# proMinimotor.net
KiCad netlist of a schematic drawn in EAGLE
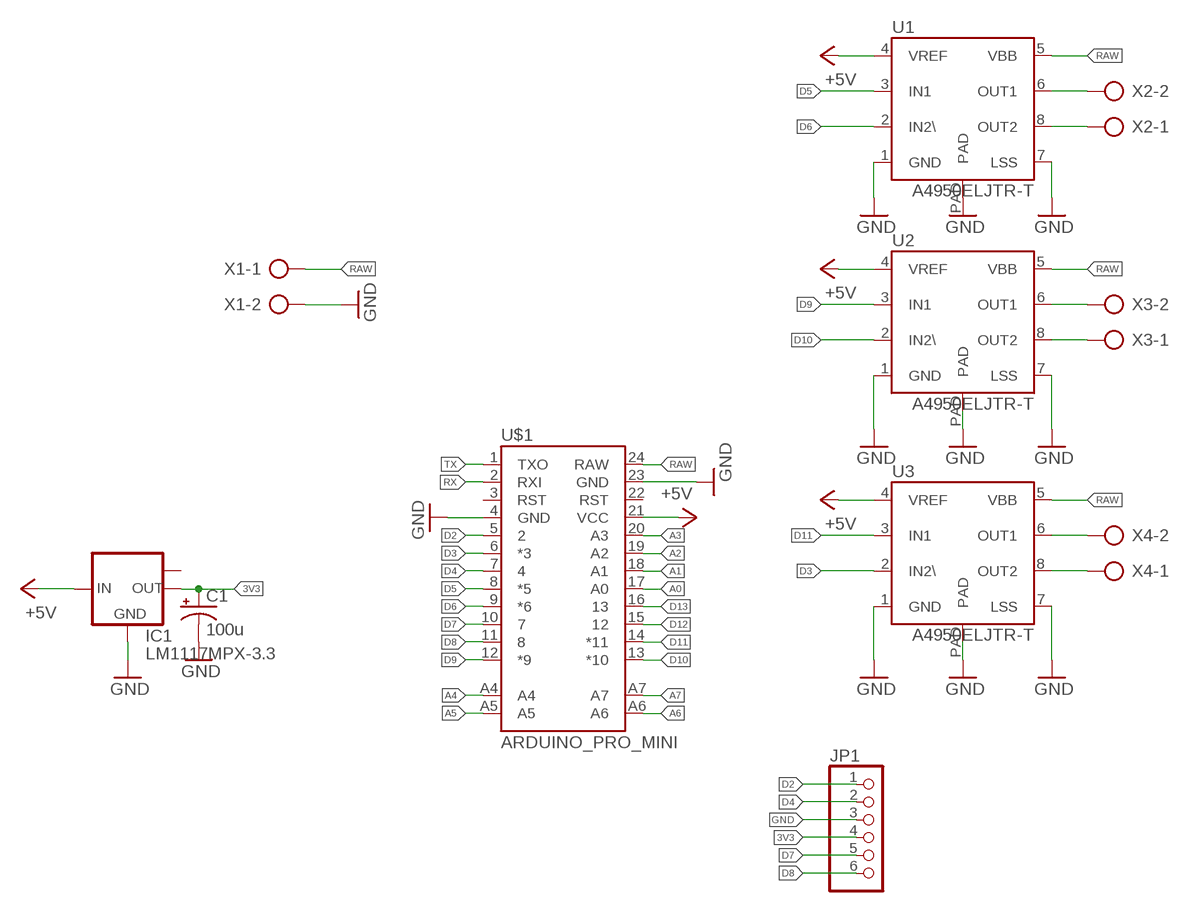
[diagram p0: schematic, sheet 1]

(export (version "E")
  (design (tool "Eeschema 10.0.6"))
  (components
    (comp (ref "C1")
      (value "100u")
      (footprint "eagle-import:E2,5-7")
      (libsource (lib "eagle-import") (part "CPOL-USE2.5-7"))
    )
    (comp (ref "IC1")
      (value "LM1117MPX-3.3")
      (footprint "eagle-import:SOT223")
      (libsource (lib "eagle-import") (part "LM1117MPX-3.3"))
    )
    (comp (ref "JP1")
      (value "PINHD-1X6/90")
      (footprint "eagle-import:1X06_90")
      (libsource (lib "eagle-import") (part "PINHD-1X6/90"))
    )
    (comp (ref "U$1")
      (value "ARDUINO_PRO_MINI")
      (footprint "eagle-import:ARDUINO_PRO_MINI")
      (libsource (lib "eagle-import") (part "ARDUINO_PRO_MINI"))
    )
    (comp (ref "U1")
      (value "A4950ELJTR-T")
      (footprint "eagle-import:SOIC8TP")
      (libsource (lib "eagle-import") (part "A4950ELJTR-T"))
    )
    (comp (ref "U2")
      (value "A4950ELJTR-T")
      (footprint "eagle-import:SOIC8TP")
      (libsource (lib "eagle-import") (part "A4950ELJTR-T"))
    )
    (comp (ref "U3")
      (value "A4950ELJTR-T")
      (footprint "eagle-import:SOIC8TP")
      (libsource (lib "eagle-import") (part "A4950ELJTR-T"))
    )
    (comp (ref "X1")
      (value "AK500/2")
      (footprint "eagle-import:AK500_2")
      (libsource (lib "eagle-import") (part "AK500/2"))
    )
    (comp (ref "X2")
      (value "AK500/2")
      (footprint "eagle-import:AK500_2")
      (libsource (lib "eagle-import") (part "AK500/2"))
    )
    (comp (ref "X3")
      (value "AK500/2")
      (footprint "eagle-import:AK500_2")
      (libsource (lib "eagle-import") (part "AK500/2"))
    )
    (comp (ref "X4")
      (value "AK500/2")
      (footprint "eagle-import:AK500_2")
      (libsource (lib "eagle-import") (part "AK500/2"))
    )
  )
  (nets
    (net (code "1") (name "+5V") (class "Default")
      (node (ref "IC1") (pin "3") (pinfunction "IN_3") (pintype "input"))
      (node (ref "U$1") (pin "21") (pinfunction "VCC_21") (pintype "bidirectional"))
      (node (ref "U1") (pin "4") (pinfunction "VREF_4") (pintype "bidirectional"))
      (node (ref "U2") (pin "4") (pinfunction "VREF_4") (pintype "bidirectional"))
      (node (ref "U3") (pin "4") (pinfunction "VREF_4") (pintype "bidirectional"))
    )
    (net (code "2") (name "3V3") (class "Default")
      (node (ref "C1") (pin "+") (pinfunction "+_+") (pintype "passive"))
      (node (ref "IC1") (pin "2") (pinfunction "OUT_2") (pintype "passive"))
      (node (ref "JP1") (pin "4") (pinfunction "4_4") (pintype "passive"))
    )
    (net (code "3") (name "A0") (class "Default")
      (node (ref "U$1") (pin "17") (pinfunction "A0_17") (pintype "bidirectional"))
    )
    (net (code "4") (name "A1") (class "Default")
      (node (ref "U$1") (pin "18") (pinfunction "A1_18") (pintype "bidirectional"))
    )
    (net (code "5") (name "A2") (class "Default")
      (node (ref "U$1") (pin "19") (pinfunction "A2_19") (pintype "bidirectional"))
    )
    (net (code "6") (name "A3") (class "Default")
      (node (ref "U$1") (pin "20") (pinfunction "A3_20") (pintype "bidirectional"))
    )
    (net (code "7") (name "A4") (class "Default")
      (node (ref "U$1") (pin "A4") (pinfunction "A4_A4") (pintype "bidirectional"))
    )
    (net (code "8") (name "A5") (class "Default")
      (node (ref "U$1") (pin "A5") (pinfunction "A5_A5") (pintype "bidirectional"))
    )
    (net (code "9") (name "A6") (class "Default")
      (node (ref "U$1") (pin "A6") (pinfunction "A6_A6") (pintype "bidirectional"))
    )
    (net (code "10") (name "A7") (class "Default")
      (node (ref "U$1") (pin "A7") (pinfunction "A7_A7") (pintype "bidirectional"))
    )
    (net (code "11") (name "D2") (class "Default")
      (node (ref "JP1") (pin "1") (pinfunction "1_1") (pintype "passive"))
      (node (ref "U$1") (pin "5") (pinfunction "2_5") (pintype "bidirectional"))
    )
    (net (code "12") (name "D3") (class "Default")
      (node (ref "U$1") (pin "6") (pinfunction "*3_6") (pintype "bidirectional"))
      (node (ref "U3") (pin "2") (pinfunction "IN2\\_2") (pintype "bidirectional"))
    )
    (net (code "13") (name "D4") (class "Default")
      (node (ref "JP1") (pin "2") (pinfunction "2_2") (pintype "passive"))
      (node (ref "U$1") (pin "7") (pinfunction "4_7") (pintype "bidirectional"))
    )
    (net (code "14") (name "D5") (class "Default")
      (node (ref "U$1") (pin "8") (pinfunction "*5_8") (pintype "bidirectional"))
      (node (ref "U1") (pin "3") (pinfunction "IN1_3") (pintype "bidirectional"))
    )
    (net (code "15") (name "D6") (class "Default")
      (node (ref "U$1") (pin "9") (pinfunction "*6_9") (pintype "bidirectional"))
      (node (ref "U1") (pin "2") (pinfunction "IN2\\_2") (pintype "bidirectional"))
    )
    (net (code "16") (name "D7") (class "Default")
      (node (ref "JP1") (pin "5") (pinfunction "5_5") (pintype "passive"))
      (node (ref "U$1") (pin "10") (pinfunction "7_10") (pintype "bidirectional"))
    )
    (net (code "17") (name "D8") (class "Default")
      (node (ref "JP1") (pin "6") (pinfunction "6_6") (pintype "passive"))
      (node (ref "U$1") (pin "11") (pinfunction "8_11") (pintype "bidirectional"))
    )
    (net (code "18") (name "D9") (class "Default")
      (node (ref "U$1") (pin "12") (pinfunction "*9_12") (pintype "bidirectional"))
      (node (ref "U2") (pin "3") (pinfunction "IN1_3") (pintype "bidirectional"))
    )
    (net (code "19") (name "D10") (class "Default")
      (node (ref "U$1") (pin "13") (pinfunction "*10_13") (pintype "bidirectional"))
      (node (ref "U2") (pin "2") (pinfunction "IN2\\_2") (pintype "bidirectional"))
    )
    (net (code "20") (name "D11") (class "Default")
      (node (ref "U$1") (pin "14") (pinfunction "*11_14") (pintype "bidirectional"))
      (node (ref "U3") (pin "3") (pinfunction "IN1_3") (pintype "bidirectional"))
    )
    (net (code "21") (name "D12") (class "Default")
      (node (ref "U$1") (pin "15") (pinfunction "12_15") (pintype "bidirectional"))
    )
    (net (code "22") (name "D13") (class "Default")
      (node (ref "U$1") (pin "16") (pinfunction "13_16") (pintype "bidirectional"))
    )
    (net (code "23") (name "GND") (class "Default")
      (node (ref "C1") (pin "-") (pinfunction "-_-") (pintype "passive"))
      (node (ref "IC1") (pin "1") (pinfunction "GND_1") (pintype "input"))
      (node (ref "JP1") (pin "3") (pinfunction "3_3") (pintype "passive"))
      (node (ref "U$1") (pin "23") (pinfunction "GND_23") (pintype "bidirectional"))
      (node (ref "U$1") (pin "4") (pinfunction "GND_4") (pintype "bidirectional"))
      (node (ref "U1") (pin "1") (pinfunction "GND_1") (pintype "bidirectional"))
      (node (ref "U1") (pin "7") (pinfunction "LSS_7") (pintype "bidirectional"))
      (node (ref "U1") (pin "PAD") (pinfunction "PAD_PAD") (pintype "bidirectional"))
      (node (ref "U2") (pin "1") (pinfunction "GND_1") (pintype "bidirectional"))
      (node (ref "U2") (pin "7") (pinfunction "LSS_7") (pintype "bidirectional"))
      (node (ref "U2") (pin "PAD") (pinfunction "PAD_PAD") (pintype "bidirectional"))
      (node (ref "U3") (pin "1") (pinfunction "GND_1") (pintype "bidirectional"))
      (node (ref "U3") (pin "7") (pinfunction "LSS_7") (pintype "bidirectional"))
      (node (ref "U3") (pin "PAD") (pinfunction "PAD_PAD") (pintype "bidirectional"))
      (node (ref "X1") (pin "2") (pinfunction "KL_2") (pintype "passive"))
    )
    (net (code "24") (name "Net-(U1-OUT1)") (class "Default")
      (node (ref "U1") (pin "6") (pinfunction "OUT1_6") (pintype "bidirectional"))
      (node (ref "X2") (pin "2") (pinfunction "KL_2") (pintype "passive"))
    )
    (net (code "25") (name "Net-(U1-OUT2)") (class "Default")
      (node (ref "U1") (pin "8") (pinfunction "OUT2_8") (pintype "bidirectional"))
      (node (ref "X2") (pin "1") (pinfunction "KL_1") (pintype "passive"))
    )
    (net (code "26") (name "Net-(U2-OUT1)") (class "Default")
      (node (ref "U2") (pin "6") (pinfunction "OUT1_6") (pintype "bidirectional"))
      (node (ref "X3") (pin "2") (pinfunction "KL_2") (pintype "passive"))
    )
    (net (code "27") (name "Net-(U2-OUT2)") (class "Default")
      (node (ref "U2") (pin "8") (pinfunction "OUT2_8") (pintype "bidirectional"))
      (node (ref "X3") (pin "1") (pinfunction "KL_1") (pintype "passive"))
    )
    (net (code "28") (name "Net-(U3-OUT1)") (class "Default")
      (node (ref "U3") (pin "6") (pinfunction "OUT1_6") (pintype "bidirectional"))
      (node (ref "X4") (pin "2") (pinfunction "KL_2") (pintype "passive"))
    )
    (net (code "29") (name "Net-(U3-OUT2)") (class "Default")
      (node (ref "U3") (pin "8") (pinfunction "OUT2_8") (pintype "bidirectional"))
      (node (ref "X4") (pin "1") (pinfunction "KL_1") (pintype "passive"))
    )
    (net (code "30") (name "RAW") (class "Default")
      (node (ref "U$1") (pin "24") (pinfunction "RAW_24") (pintype "bidirectional"))
      (node (ref "U1") (pin "5") (pinfunction "VBB_5") (pintype "bidirectional"))
      (node (ref "U2") (pin "5") (pinfunction "VBB_5") (pintype "bidirectional"))
      (node (ref "U3") (pin "5") (pinfunction "VBB_5") (pintype "bidirectional"))
      (node (ref "X1") (pin "1") (pinfunction "KL_1") (pintype "passive"))
    )
    (net (code "31") (name "RX") (class "Default")
      (node (ref "U$1") (pin "2") (pinfunction "RXI_2") (pintype "bidirectional"))
    )
    (net (code "32") (name "TX") (class "Default")
      (node (ref "U$1") (pin "1") (pinfunction "TXO_1") (pintype "bidirectional"))
    )
    (net (code "33") (name "unconnected-(IC1-OUT1-PadTAB)") (class "Default")
      (node (ref "IC1") (pin "TAB") (pinfunction "OUT1_TAB") (pintype "passive"))
    )
    (net (code "34") (name "unconnected-(U$1-RST-Pad3)") (class "Default")
      (node (ref "U$1") (pin "3") (pinfunction "RST_3") (pintype "bidirectional"))
    )
    (net (code "35") (name "unconnected-(U$1-RST-Pad22)") (class "Default")
      (node (ref "U$1") (pin "22") (pinfunction "RST_22") (pintype "bidirectional"))
    )
  )
)
